# RatDBS-Compact2032Battery.net
KiCad netlist of a schematic drawn in EAGLE
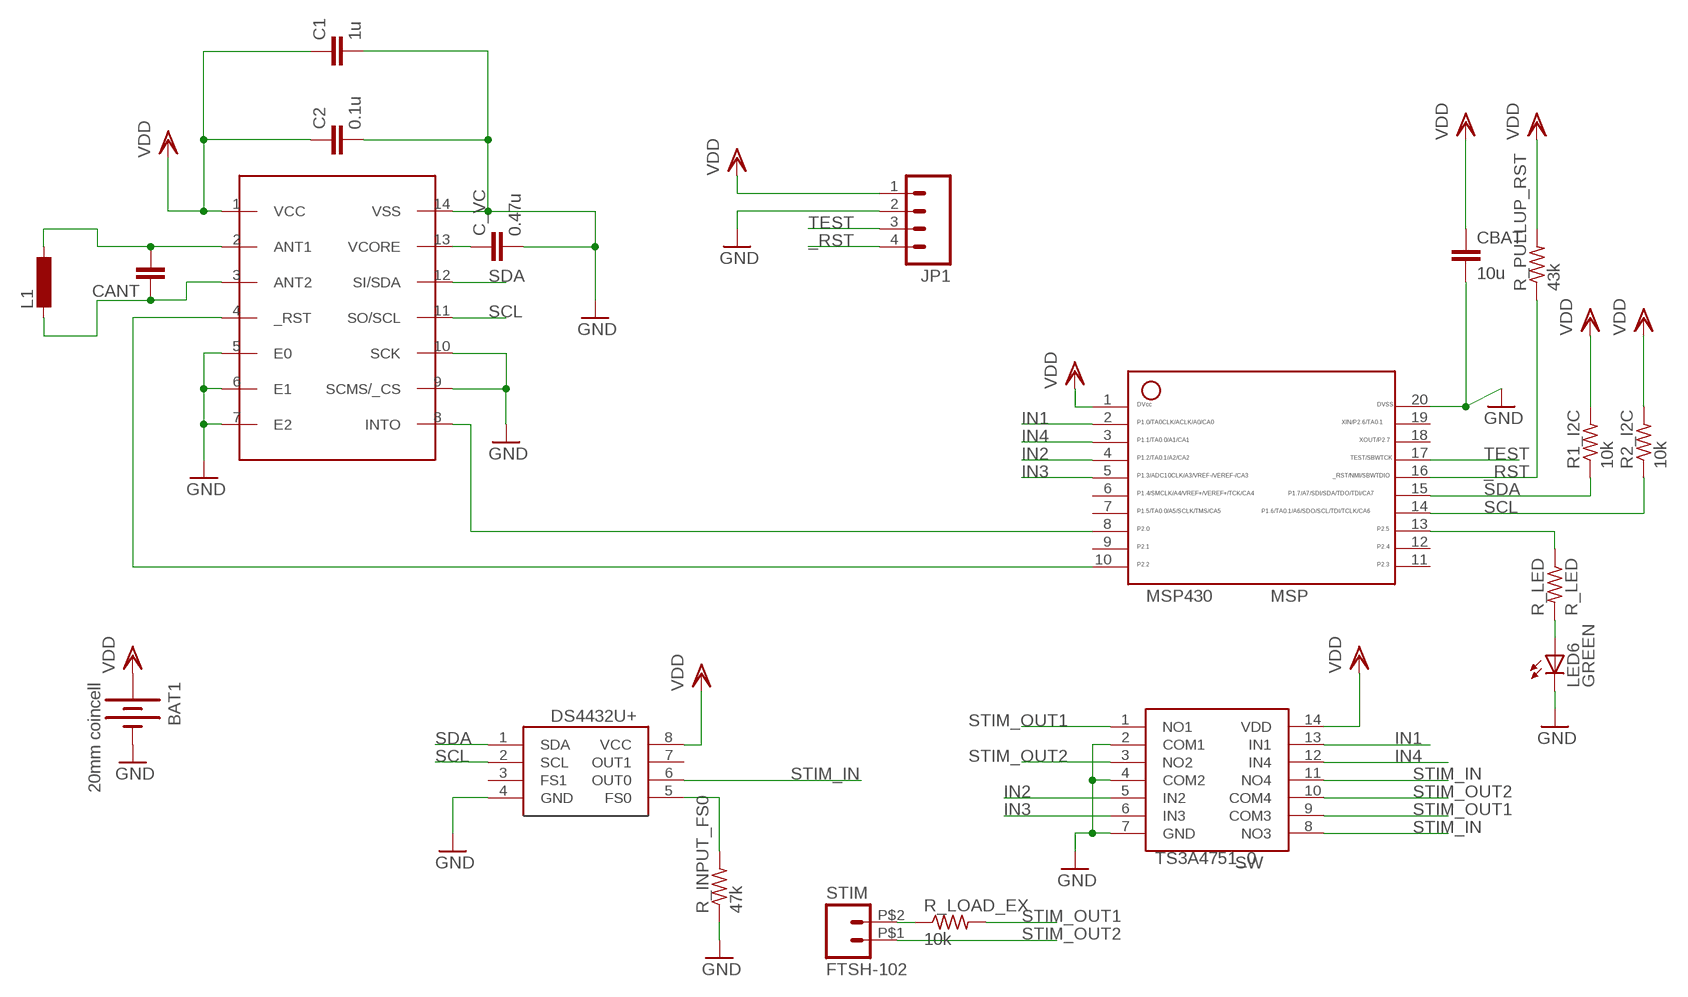
[diagram p0: schematic, sheet 1]

(export (version "E")
  (design (tool "Eeschema 10.0.6"))
  (components
    (comp (ref "BAT1")
      (value "20mm coincell")
      (footprint "eagle-import:BATTCON_20MM_PTH_COMPACT")
      (libsource (lib "eagle-import") (part "BATTERYFOB"))
    )
    (comp (ref "C1")
      (value "1u")
      (footprint "eagle-import:C0603")
      (libsource (lib "eagle-import") (part "C-EUC0603"))
    )
    (comp (ref "C2")
      (value "0.1u")
      (footprint "eagle-import:C0603")
      (libsource (lib "eagle-import") (part "C-EUC0603"))
    )
    (comp (ref "CANT")
      (value "C-EUC0603")
      (footprint "eagle-import:C0603")
      (libsource (lib "eagle-import") (part "C-EUC0603"))
    )
    (comp (ref "CBAT")
      (value "10u")
      (footprint "eagle-import:C0603")
      (libsource (lib "eagle-import") (part "C-EUC0603"))
    )
    (comp (ref "C_VC")
      (value "0.47u")
      (footprint "eagle-import:C0603")
      (libsource (lib "eagle-import") (part "C-EUC0603"))
    )
    (comp (ref "DS4432U+")
      (value "DS4432U+")
      (footprint "eagle-import:8_PIN")
      (libsource (lib "eagle-import") (part "DS4432U+"))
    )
    (comp (ref "JP1")
      (value "M041.27MM")
      (footprint "eagle-import:1X04-1.27MM")
      (libsource (lib "eagle-import") (part "M041.27MM"))
    )
    (comp (ref "L1")
      (value "L-EUWE-TPC")
      (footprint "eagle-import:POWER-CHOKE_WE-TPC")
      (libsource (lib "eagle-import") (part "L-EUWE-TPC"))
    )
    (comp (ref "LED6")
      (value "GREEN")
      (footprint "eagle-import:LED-1206")
      (libsource (lib "eagle-import") (part "LED1206"))
    )
    (comp (ref "MSP430")
      (value "MSP")
      (footprint "eagle-import:20_PIN")
      (libsource (lib "eagle-import") (part "MSP430"))
    )
    (comp (ref "R1_I2C")
      (value "10k")
      (footprint "eagle-import:R0603")
      (libsource (lib "eagle-import") (part "R-US_R0603"))
    )
    (comp (ref "R2_I2C")
      (value "10k")
      (footprint "eagle-import:R0603")
      (libsource (lib "eagle-import") (part "R-US_R0603"))
    )
    (comp (ref "R_INPUT_FS0")
      (value "47k")
      (footprint "eagle-import:R0603")
      (libsource (lib "eagle-import") (part "R-US_R0603"))
    )
    (comp (ref "R_LED")
      (value "R_LED")
      (footprint "eagle-import:R0603")
      (libsource (lib "eagle-import") (part "R-US_R0603"))
    )
    (comp (ref "R_LOAD_EX")
      (value "10k")
      (footprint "eagle-import:R0603")
      (libsource (lib "eagle-import") (part "R-US_R0603"))
    )
    (comp (ref "R_PULLUP_RST")
      (value "43k")
      (footprint "eagle-import:R0603")
      (libsource (lib "eagle-import") (part "R-US_R0603"))
    )
    (comp (ref "STIM")
      (value "FTSH-102")
      (footprint "eagle-import:FTSH-102-DH")
      (libsource (lib "eagle-import") (part "FTSH-102"))
    )
    (comp (ref "TS3A4751_0")
      (value "SW")
      (footprint "eagle-import:14_PIN")
      (libsource (lib "eagle-import") (part "TS3A4751"))
    )
    (comp (ref "U$1")
      (value "RF")
      (footprint "eagle-import:PW_R-PDSO-G14")
      (libsource (lib "eagle-import") (part "RF430CL330H"))
    )
  )
  (nets
    (net (code "1") (name "/IN1") (class "Default")
      (node (ref "MSP430") (pin "2") (pinfunction "2_2") (pintype "bidirectional"))
      (node (ref "TS3A4751_0") (pin "13") (pinfunction "IN1_13") (pintype "bidirectional"))
    )
    (net (code "2") (name "/IN2") (class "Default")
      (node (ref "MSP430") (pin "4") (pinfunction "4_4") (pintype "bidirectional"))
      (node (ref "TS3A4751_0") (pin "5") (pinfunction "IN2_5") (pintype "bidirectional"))
    )
    (net (code "3") (name "/IN3") (class "Default")
      (node (ref "MSP430") (pin "5") (pinfunction "5_5") (pintype "bidirectional"))
      (node (ref "TS3A4751_0") (pin "6") (pinfunction "IN3_6") (pintype "bidirectional"))
    )
    (net (code "4") (name "/IN4") (class "Default")
      (node (ref "MSP430") (pin "3") (pinfunction "3_3") (pintype "bidirectional"))
      (node (ref "TS3A4751_0") (pin "12") (pinfunction "IN4_12") (pintype "bidirectional"))
    )
    (net (code "5") (name "/SCL") (class "Default")
      (node (ref "DS4432U+") (pin "2") (pinfunction "SCL_2") (pintype "bidirectional"))
      (node (ref "MSP430") (pin "14") (pinfunction "14_14") (pintype "bidirectional"))
      (node (ref "R2_I2C") (pin "1") (pinfunction "1_1") (pintype "passive"))
      (node (ref "U$1") (pin "11") (pinfunction "SO/SCL_11") (pintype "bidirectional"))
    )
    (net (code "6") (name "/SDA") (class "Default")
      (node (ref "DS4432U+") (pin "1") (pinfunction "SDA_1") (pintype "bidirectional"))
      (node (ref "MSP430") (pin "15") (pinfunction "15_15") (pintype "bidirectional"))
      (node (ref "R1_I2C") (pin "1") (pinfunction "1_1") (pintype "passive"))
      (node (ref "U$1") (pin "12") (pinfunction "SI/SDA_12") (pintype "bidirectional"))
    )
    (net (code "7") (name "/STIM_IN") (class "Default")
      (node (ref "DS4432U+") (pin "6") (pinfunction "OUT0_6") (pintype "bidirectional"))
      (node (ref "TS3A4751_0") (pin "11") (pinfunction "NO4_11") (pintype "bidirectional"))
      (node (ref "TS3A4751_0") (pin "8") (pinfunction "NO3_8") (pintype "bidirectional"))
    )
    (net (code "8") (name "/STIM_OUT1") (class "Default")
      (node (ref "R_LOAD_EX") (pin "2") (pinfunction "2_2") (pintype "passive"))
      (node (ref "TS3A4751_0") (pin "1") (pinfunction "NO1_1") (pintype "bidirectional"))
      (node (ref "TS3A4751_0") (pin "9") (pinfunction "COM3_9") (pintype "bidirectional"))
    )
    (net (code "9") (name "/STIM_OUT2") (class "Default")
      (node (ref "STIM") (pin "P$1") (pinfunction "1_P$1") (pintype "passive"))
      (node (ref "TS3A4751_0") (pin "10") (pinfunction "COM4_10") (pintype "bidirectional"))
      (node (ref "TS3A4751_0") (pin "3") (pinfunction "NO2_3") (pintype "bidirectional"))
    )
    (net (code "10") (name "/TEST") (class "Default")
      (node (ref "JP1") (pin "3") (pinfunction "3_3") (pintype "passive"))
      (node (ref "MSP430") (pin "17") (pinfunction "17_17") (pintype "bidirectional"))
    )
    (net (code "11") (name "/_RST") (class "Default")
      (node (ref "JP1") (pin "4") (pinfunction "4_4") (pintype "passive"))
      (node (ref "MSP430") (pin "16") (pinfunction "16_16") (pintype "bidirectional"))
      (node (ref "R_PULLUP_RST") (pin "1") (pinfunction "1_1") (pintype "passive"))
    )
    (net (code "12") (name "GND") (class "Default")
      (node (ref "BAT1") (pin "2") (pinfunction "-_2") (pintype "power_in"))
      (node (ref "C1") (pin "2") (pinfunction "2_2") (pintype "passive"))
      (node (ref "C2") (pin "2") (pinfunction "2_2") (pintype "passive"))
      (node (ref "CBAT") (pin "2") (pinfunction "2_2") (pintype "passive"))
      (node (ref "C_VC") (pin "2") (pinfunction "2_2") (pintype "passive"))
      (node (ref "DS4432U+") (pin "4") (pinfunction "GND_4") (pintype "power_in"))
      (node (ref "JP1") (pin "2") (pinfunction "2_2") (pintype "passive"))
      (node (ref "LED6") (pin "C") (pinfunction "C_C") (pintype "passive"))
      (node (ref "MSP430") (pin "20") (pinfunction "20_20") (pintype "bidirectional"))
      (node (ref "R_INPUT_FS0") (pin "1") (pinfunction "1_1") (pintype "passive"))
      (node (ref "TS3A4751_0") (pin "2") (pinfunction "COM1_2") (pintype "bidirectional"))
      (node (ref "TS3A4751_0") (pin "4") (pinfunction "COM2_4") (pintype "bidirectional"))
      (node (ref "TS3A4751_0") (pin "7") (pinfunction "GND_7") (pintype "bidirectional"))
      (node (ref "U$1") (pin "10") (pinfunction "SCK_10") (pintype "bidirectional"))
      (node (ref "U$1") (pin "14") (pinfunction "VSS_14") (pintype "power_in"))
      (node (ref "U$1") (pin "5") (pinfunction "E0_5") (pintype "bidirectional"))
      (node (ref "U$1") (pin "6") (pinfunction "E1_6") (pintype "bidirectional"))
      (node (ref "U$1") (pin "7") (pinfunction "E2_7") (pintype "bidirectional"))
      (node (ref "U$1") (pin "9") (pinfunction "SCMS/_CS_9") (pintype "bidirectional"))
    )
    (net (code "13") (name "Net-(DS4432U+-FS0)") (class "Default")
      (node (ref "DS4432U+") (pin "5") (pinfunction "FS0_5") (pintype "bidirectional"))
      (node (ref "R_INPUT_FS0") (pin "2") (pinfunction "2_2") (pintype "passive"))
    )
    (net (code "14") (name "Net-(LED6-PadA)") (class "Default")
      (node (ref "LED6") (pin "A") (pinfunction "A_A") (pintype "passive"))
      (node (ref "R_LED") (pin "2") (pinfunction "2_2") (pintype "passive"))
    )
    (net (code "15") (name "Net-(MSP430-Pad13)") (class "Default")
      (node (ref "MSP430") (pin "13") (pinfunction "13_13") (pintype "bidirectional"))
      (node (ref "R_LED") (pin "1") (pinfunction "1_1") (pintype "passive"))
    )
    (net (code "16") (name "Net-(STIM-2)") (class "Default")
      (node (ref "R_LOAD_EX") (pin "1") (pinfunction "1_1") (pintype "passive"))
      (node (ref "STIM") (pin "P$2") (pinfunction "2_P$2") (pintype "passive"))
    )
    (net (code "17") (name "Net-(U$1-ANT1)") (class "Default")
      (node (ref "CANT") (pin "2") (pinfunction "2_2") (pintype "passive"))
      (node (ref "L1") (pin "1") (pinfunction "1_1") (pintype "passive"))
      (node (ref "U$1") (pin "2") (pinfunction "ANT1_2") (pintype "bidirectional"))
    )
    (net (code "18") (name "Net-(U$1-ANT2)") (class "Default")
      (node (ref "CANT") (pin "1") (pinfunction "1_1") (pintype "passive"))
      (node (ref "L1") (pin "2") (pinfunction "2_2") (pintype "passive"))
      (node (ref "U$1") (pin "3") (pinfunction "ANT2_3") (pintype "bidirectional"))
    )
    (net (code "19") (name "Net-(U$1-INTO)") (class "Default")
      (node (ref "MSP430") (pin "8") (pinfunction "8_8") (pintype "bidirectional"))
      (node (ref "U$1") (pin "8") (pinfunction "INTO_8") (pintype "bidirectional"))
    )
    (net (code "20") (name "Net-(U$1-VCORE)") (class "Default")
      (node (ref "C_VC") (pin "1") (pinfunction "1_1") (pintype "passive"))
      (node (ref "U$1") (pin "13") (pinfunction "VCORE_13") (pintype "bidirectional"))
    )
    (net (code "21") (name "Net-(U$1-_RST)") (class "Default")
      (node (ref "MSP430") (pin "10") (pinfunction "10_10") (pintype "bidirectional"))
      (node (ref "U$1") (pin "4") (pinfunction "_RST_4") (pintype "bidirectional"))
    )
    (net (code "22") (name "VDD") (class "Default")
      (node (ref "BAT1") (pin "1") (pinfunction "+_1") (pintype "power_in"))
      (node (ref "BAT1") (pin "3") (pinfunction "+_3") (pintype "power_in"))
      (node (ref "BAT1") (pin "4") (pinfunction "+_4") (pintype "power_in"))
      (node (ref "BAT1") (pin "5") (pinfunction "+_5") (pintype "power_in"))
      (node (ref "C1") (pin "1") (pinfunction "1_1") (pintype "passive"))
      (node (ref "C2") (pin "1") (pinfunction "1_1") (pintype "passive"))
      (node (ref "CBAT") (pin "1") (pinfunction "1_1") (pintype "passive"))
      (node (ref "DS4432U+") (pin "8") (pinfunction "VCC_8") (pintype "power_in"))
      (node (ref "JP1") (pin "1") (pinfunction "1_1") (pintype "passive"))
      (node (ref "MSP430") (pin "1") (pinfunction "1_1") (pintype "bidirectional"))
      (node (ref "R1_I2C") (pin "2") (pinfunction "2_2") (pintype "passive"))
      (node (ref "R2_I2C") (pin "2") (pinfunction "2_2") (pintype "passive"))
      (node (ref "R_PULLUP_RST") (pin "2") (pinfunction "2_2") (pintype "passive"))
      (node (ref "TS3A4751_0") (pin "14") (pinfunction "VDD_14") (pintype "bidirectional"))
      (node (ref "U$1") (pin "1") (pinfunction "VCC_1") (pintype "power_in"))
    )
    (net (code "23") (name "unconnected-(DS4432U+-FS1-Pad3)") (class "Default")
      (node (ref "DS4432U+") (pin "3") (pinfunction "FS1_3") (pintype "bidirectional"))
    )
    (net (code "24") (name "unconnected-(DS4432U+-OUT1-Pad7)") (class "Default")
      (node (ref "DS4432U+") (pin "7") (pinfunction "OUT1_7") (pintype "bidirectional"))
    )
    (net (code "25") (name "unconnected-(MSP430-Pad6)") (class "Default")
      (node (ref "MSP430") (pin "6") (pinfunction "6_6") (pintype "bidirectional"))
    )
    (net (code "26") (name "unconnected-(MSP430-Pad7)") (class "Default")
      (node (ref "MSP430") (pin "7") (pinfunction "7_7") (pintype "bidirectional"))
    )
    (net (code "27") (name "unconnected-(MSP430-Pad9)") (class "Default")
      (node (ref "MSP430") (pin "9") (pinfunction "9_9") (pintype "bidirectional"))
    )
    (net (code "28") (name "unconnected-(MSP430-Pad11)") (class "Default")
      (node (ref "MSP430") (pin "11") (pinfunction "11_11") (pintype "bidirectional"))
    )
    (net (code "29") (name "unconnected-(MSP430-Pad12)") (class "Default")
      (node (ref "MSP430") (pin "12") (pinfunction "12_12") (pintype "bidirectional"))
    )
    (net (code "30") (name "unconnected-(MSP430-Pad18)") (class "Default")
      (node (ref "MSP430") (pin "18") (pinfunction "18_18") (pintype "bidirectional"))
    )
    (net (code "31") (name "unconnected-(MSP430-Pad19)") (class "Default")
      (node (ref "MSP430") (pin "19") (pinfunction "19_19") (pintype "bidirectional"))
    )
  )
)
